# Sheet1.net
KiCad netlist of a schematic drawn in Altium Designer
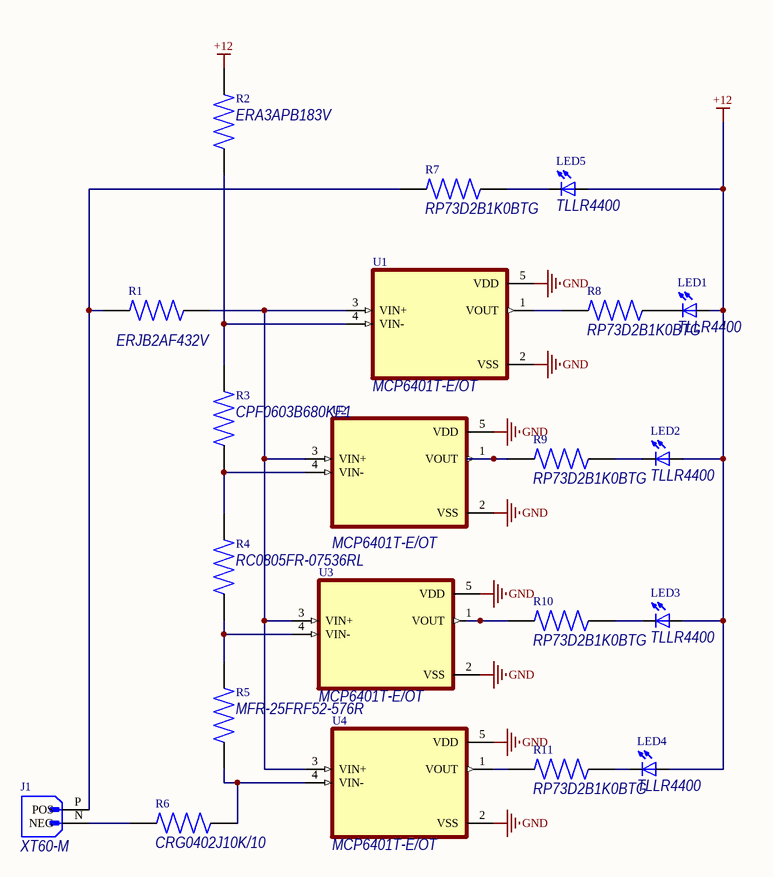
[diagram p0: Sheet1.SchDoc]

(export (version "E")
  (design (tool "Eeschema 10.0.6"))
  (components
    (comp (ref "J1")
      (value "XT60-M")
      (footprint "AMASS_XT60-M")
      (description "Plug; DC supply; XT60; male; PIN: 2; for cable; soldered; 30A; 500V")
      (fields (field (name "MF") "AMASS"))
      (libsource (lib "XT60-M") (part "XT60-M"))
    )
    (comp (ref "LED1")
      (value "TLLR4400")
      (footprint "LED3MM")
      (description "Red 619nm LED Indication - Discrete 1.9V Radial")
      (fields (field (name "MF") "Vishay"))
      (libsource (lib "TLLR4400") (part "TLLR4400"))
    )
    (comp (ref "LED2")
      (value "TLLR4400")
      (footprint "LED3MM")
      (description "Red 619nm LED Indication - Discrete 1.9V Radial")
      (fields (field (name "MF") "Vishay"))
      (libsource (lib "TLLR4400") (part "TLLR4400"))
    )
    (comp (ref "LED3")
      (value "TLLR4400")
      (footprint "LED3MM")
      (description "Red 619nm LED Indication - Discrete 1.9V Radial")
      (fields (field (name "MF") "Vishay"))
      (libsource (lib "TLLR4400") (part "TLLR4400"))
    )
    (comp (ref "LED4")
      (value "TLLR4400")
      (footprint "LED3MM")
      (description "Red 619nm LED Indication - Discrete 1.9V Radial")
      (fields (field (name "MF") "Vishay"))
      (libsource (lib "TLLR4400") (part "TLLR4400"))
    )
    (comp (ref "LED5")
      (value "TLLR4400")
      (footprint "LED3MM")
      (description "Red 619nm LED Indication - Discrete 1.9V Radial")
      (fields (field (name "MF") "Vishay"))
      (libsource (lib "TLLR4400") (part "TLLR4400"))
    )
    (comp (ref "R1")
      (value "ERJB2AF432V")
      (footprint "RES_ERJB2AF432V")
      (libsource (lib "ERJB2AF432V") (part "ERJB2AF432V"))
    )
    (comp (ref "R2")
      (value "ERA3APB183V")
      (footprint "RES_ERA3APB183V")
      (libsource (lib "ERA3APB183V") (part "ERA3APB183V"))
    )
    (comp (ref "R3")
      (value "CPF0603B680KE1")
      (footprint "RESC1508X55N")
      (description "680 kOhms Â±0.1% 0.063W, 1/16W Chip Resistor 0603 (1608 Metric) Thin Film")
      (fields (field (name "MF") "TE Connectivity") (field (name "TOLERANCE") ".1%"))
      (libsource (lib "CPF0603B680KE1") (part "CPF0603B680KE1"))
    )
    (comp (ref "R4")
      (value "RC0805FR-07536RL")
      (footprint "RESC2012X60N")
      (description "536 Ohms Â±1% 0.125W, 1/8W Chip Resistor 0805 (2012 Metric) Moisture Resistant Thick Film")
      (fields (field (name "MF") "Yageo"))
      (libsource (lib "RC0805FR-07536RL") (part "RC0805FR-07536RL"))
    )
    (comp (ref "R5")
      (value "MFR-25FRF52-576R")
      (footprint "RESAD1100W55L680D260")
      (description "576 Ohms Â±1% 0.25W, 1/4W Through Hole Resistor Axial - Metal Film")
      (fields (field (name "MF") "Yageo"))
      (libsource (lib "MFR-25FRF52-576R") (part "MFR-25FRF52-576R"))
    )
    (comp (ref "R6")
      (value "CRG0402J10K/10")
      (footprint "RESC1005X40N")
      (description "CRG0402 chip resistor,10K 5% 0.063W ¦ TE Connectivity CRG0402J10K/10")
      (fields (field (name "MF") "TE Connectivity") (field (name "TOLERANCE") "5%"))
      (libsource (lib "CRG0402J10K_10") (part "CRG0402J10K/10"))
    )
    (comp (ref "R7")
      (value "RP73D2B1K0BTG")
      (footprint "RESC3015X65N")
      (description "Res Thin Film 1206 1K Ohm 0.1% 0.25W(1/4W) Â±15ppm/C Epoxy Pad SMD Medical T/R")
      (fields (field (name "MF") "TE Connectivity") (field (name "TOLERANCE") ".1%"))
      (libsource (lib "RP73D2B1K0BTG") (part "RP73D2B1K0BTG"))
    )
    (comp (ref "R8")
      (value "RP73D2B1K0BTG")
      (footprint "RESC3015X65N")
      (description "Res Thin Film 1206 1K Ohm 0.1% 0.25W(1/4W) Â±15ppm/C Epoxy Pad SMD Medical T/R")
      (fields (field (name "MF") "TE Connectivity") (field (name "TOLERANCE") ".1%"))
      (libsource (lib "RP73D2B1K0BTG") (part "RP73D2B1K0BTG"))
    )
    (comp (ref "R9")
      (value "RP73D2B1K0BTG")
      (footprint "RESC3015X65N")
      (description "Res Thin Film 1206 1K Ohm 0.1% 0.25W(1/4W) Â±15ppm/C Epoxy Pad SMD Medical T/R")
      (fields (field (name "MF") "TE Connectivity") (field (name "TOLERANCE") ".1%"))
      (libsource (lib "RP73D2B1K0BTG") (part "RP73D2B1K0BTG"))
    )
    (comp (ref "R10")
      (value "RP73D2B1K0BTG")
      (footprint "RESC3015X65N")
      (description "Res Thin Film 1206 1K Ohm 0.1% 0.25W(1/4W) Â±15ppm/C Epoxy Pad SMD Medical T/R")
      (fields (field (name "MF") "TE Connectivity") (field (name "TOLERANCE") ".1%"))
      (libsource (lib "RP73D2B1K0BTG") (part "RP73D2B1K0BTG"))
    )
    (comp (ref "R11")
      (value "RP73D2B1K0BTG")
      (footprint "RESC3015X65N")
      (description "Res Thin Film 1206 1K Ohm 0.1% 0.25W(1/4W) Â±15ppm/C Epoxy Pad SMD Medical T/R")
      (fields (field (name "MF") "TE Connectivity") (field (name "TOLERANCE") ".1%"))
      (libsource (lib "RP73D2B1K0BTG") (part "RP73D2B1K0BTG"))
    )
    (comp (ref "U1")
      (value "MCP6401T-E/OT")
      (footprint "SOT95P270X145-5N")
      (description "General Purpose Amplifier 1 Circuit Rail-to-Rail SOT-23-5")
      (fields (field (name "DIGI-KEY_PART_NUMBER") "MCP6401T-E/OTCT-ND") (field (name "MF") "Microchip"))
      (libsource (lib "MCP6401T-E_OT") (part "MCP6401T-E/OT"))
    )
    (comp (ref "U2")
      (value "MCP6401T-E/OT")
      (footprint "SOT95P270X145-5N")
      (description "General Purpose Amplifier 1 Circuit Rail-to-Rail SOT-23-5")
      (fields (field (name "DIGI-KEY_PART_NUMBER") "MCP6401T-E/OTCT-ND") (field (name "MF") "Microchip"))
      (libsource (lib "MCP6401T-E_OT") (part "MCP6401T-E/OT"))
    )
    (comp (ref "U3")
      (value "MCP6401T-E/OT")
      (footprint "SOT95P270X145-5N")
      (description "General Purpose Amplifier 1 Circuit Rail-to-Rail SOT-23-5")
      (fields (field (name "DIGI-KEY_PART_NUMBER") "MCP6401T-E/OTCT-ND") (field (name "MF") "Microchip"))
      (libsource (lib "MCP6401T-E_OT") (part "MCP6401T-E/OT"))
    )
    (comp (ref "U4")
      (value "MCP6401T-E/OT")
      (footprint "SOT95P270X145-5N")
      (description "General Purpose Amplifier 1 Circuit Rail-to-Rail SOT-23-5")
      (fields (field (name "DIGI-KEY_PART_NUMBER") "MCP6401T-E/OTCT-ND") (field (name "MF") "Microchip"))
      (libsource (lib "MCP6401T-E_OT") (part "MCP6401T-E/OT"))
    )
  )
  (nets
    (net (code "1") (name "+12") (class "Default")
      (node (ref "LED1") (pin "A") (pinfunction "A_A") (pintype "passive"))
      (node (ref "LED2") (pin "A") (pinfunction "A_A") (pintype "passive"))
      (node (ref "LED3") (pin "A") (pinfunction "A_A") (pintype "passive"))
      (node (ref "LED4") (pin "A") (pinfunction "A_A") (pintype "passive"))
      (node (ref "LED5") (pin "A") (pinfunction "A_A") (pintype "passive"))
      (node (ref "R2") (pin "2") (pinfunction "2_2") (pintype "passive"))
    )
    (net (code "2") (name "GND") (class "Default")
      (node (ref "U1") (pin "2") (pinfunction "VSS_2") (pintype "power_in"))
      (node (ref "U1") (pin "5") (pinfunction "VDD_5") (pintype "power_in"))
      (node (ref "U2") (pin "2") (pinfunction "VSS_2") (pintype "power_in"))
      (node (ref "U2") (pin "5") (pinfunction "VDD_5") (pintype "power_in"))
      (node (ref "U3") (pin "2") (pinfunction "VSS_2") (pintype "power_in"))
      (node (ref "U3") (pin "5") (pinfunction "VDD_5") (pintype "power_in"))
      (node (ref "U4") (pin "2") (pinfunction "VSS_2") (pintype "power_in"))
      (node (ref "U4") (pin "5") (pinfunction "VDD_5") (pintype "power_in"))
    )
    (net (code "3") (name "Net-(J1-NEG)") (class "Default")
      (node (ref "J1") (pin "N") (pinfunction "NEG_N") (pintype "passive"))
      (node (ref "R6") (pin "1") (pinfunction "1_1") (pintype "passive"))
    )
    (net (code "4") (name "Net-(J1-POS)") (class "Default")
      (node (ref "J1") (pin "P") (pinfunction "POS_P") (pintype "passive"))
      (node (ref "R1") (pin "1") (pinfunction "1_1") (pintype "passive"))
      (node (ref "R7") (pin "1") (pinfunction "1_1") (pintype "passive"))
    )
    (net (code "5") (name "Net-(LED1-C)") (class "Default")
      (node (ref "LED1") (pin "K") (pinfunction "C_K") (pintype "passive"))
      (node (ref "R8") (pin "2") (pinfunction "2_2") (pintype "passive"))
    )
    (net (code "6") (name "Net-(LED2-C)") (class "Default")
      (node (ref "LED2") (pin "K") (pinfunction "C_K") (pintype "passive"))
      (node (ref "R9") (pin "2") (pinfunction "2_2") (pintype "passive"))
    )
    (net (code "7") (name "Net-(LED3-C)") (class "Default")
      (node (ref "LED3") (pin "K") (pinfunction "C_K") (pintype "passive"))
      (node (ref "R10") (pin "2") (pinfunction "2_2") (pintype "passive"))
    )
    (net (code "8") (name "Net-(LED4-C)") (class "Default")
      (node (ref "LED4") (pin "K") (pinfunction "C_K") (pintype "passive"))
      (node (ref "R11") (pin "2") (pinfunction "2_2") (pintype "passive"))
    )
    (net (code "9") (name "Net-(LED5-C)") (class "Default")
      (node (ref "LED5") (pin "K") (pinfunction "C_K") (pintype "passive"))
      (node (ref "R7") (pin "2") (pinfunction "2_2") (pintype "passive"))
    )
    (net (code "10") (name "Net-(U1-VIN+)") (class "Default")
      (node (ref "R1") (pin "2") (pinfunction "2_2") (pintype "passive"))
      (node (ref "U1") (pin "3") (pinfunction "VIN+_3") (pintype "input"))
      (node (ref "U2") (pin "3") (pinfunction "VIN+_3") (pintype "input"))
      (node (ref "U3") (pin "3") (pinfunction "VIN+_3") (pintype "input"))
      (node (ref "U4") (pin "3") (pinfunction "VIN+_3") (pintype "input"))
    )
    (net (code "11") (name "Net-(U1-VIN-)") (class "Default")
      (node (ref "R2") (pin "1") (pinfunction "1_1") (pintype "passive"))
      (node (ref "R3") (pin "2") (pinfunction "2_2") (pintype "passive"))
      (node (ref "U1") (pin "4") (pinfunction "VIN-_4") (pintype "input"))
    )
    (net (code "12") (name "Net-(U1-VOUT)") (class "Default")
      (node (ref "R8") (pin "1") (pinfunction "1_1") (pintype "passive"))
      (node (ref "U1") (pin "1") (pinfunction "VOUT_1") (pintype "output"))
    )
    (net (code "13") (name "Net-(U2-VIN-)") (class "Default")
      (node (ref "R3") (pin "1") (pinfunction "1_1") (pintype "passive"))
      (node (ref "R4") (pin "2") (pinfunction "2_2") (pintype "passive"))
      (node (ref "U2") (pin "4") (pinfunction "VIN-_4") (pintype "input"))
    )
    (net (code "14") (name "Net-(U2-VOUT)") (class "Default")
      (node (ref "R9") (pin "1") (pinfunction "1_1") (pintype "passive"))
      (node (ref "U2") (pin "1") (pinfunction "VOUT_1") (pintype "output"))
    )
    (net (code "15") (name "Net-(U3-VIN-)") (class "Default")
      (node (ref "R4") (pin "1") (pinfunction "1_1") (pintype "passive"))
      (node (ref "R5") (pin "2") (pinfunction "2_2") (pintype "passive"))
      (node (ref "U3") (pin "4") (pinfunction "VIN-_4") (pintype "input"))
    )
    (net (code "16") (name "Net-(U3-VOUT)") (class "Default")
      (node (ref "R10") (pin "1") (pinfunction "1_1") (pintype "passive"))
      (node (ref "U3") (pin "1") (pinfunction "VOUT_1") (pintype "output"))
    )
    (net (code "17") (name "Net-(U4-VIN-)") (class "Default")
      (node (ref "R5") (pin "1") (pinfunction "1_1") (pintype "passive"))
      (node (ref "R6") (pin "2") (pinfunction "2_2") (pintype "passive"))
      (node (ref "U4") (pin "4") (pinfunction "VIN-_4") (pintype "input"))
    )
    (net (code "18") (name "Net-(U4-VOUT)") (class "Default")
      (node (ref "R11") (pin "1") (pinfunction "1_1") (pintype "passive"))
      (node (ref "U4") (pin "1") (pinfunction "VOUT_1") (pintype "output"))
    )
  )
)
